# MCU_Control.net
KiCad netlist of a schematic drawn in Altium Designer
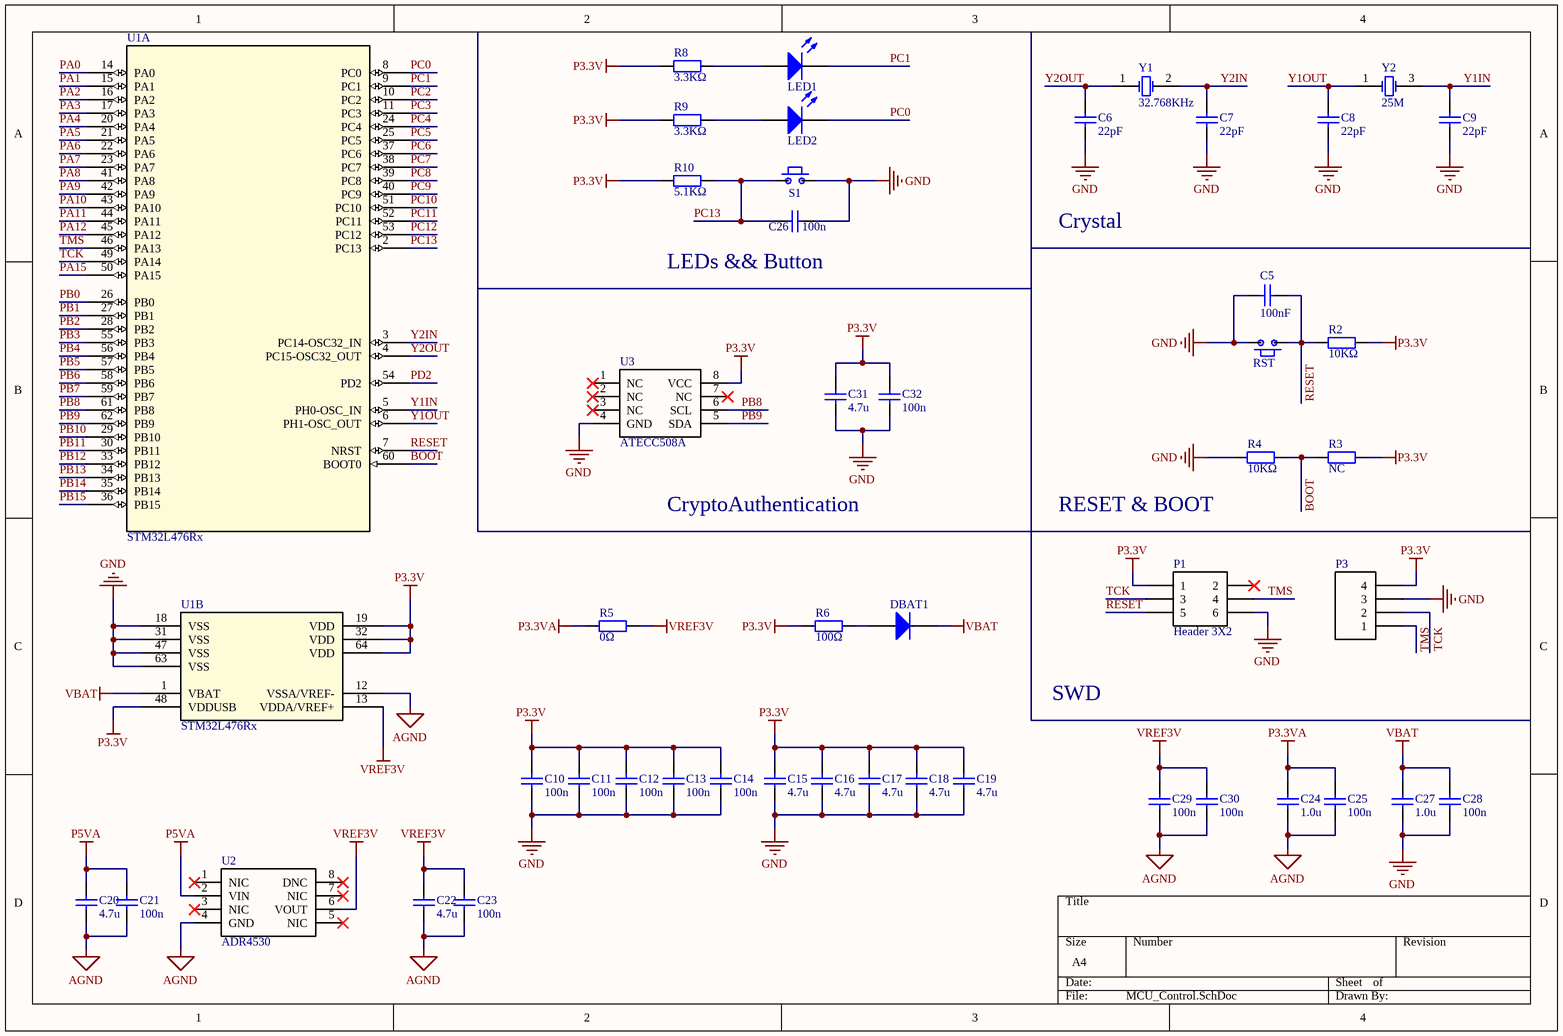
[diagram p0: MCU_Control.SchDoc]

(export (version "E")
  (design (tool "Eeschema 10.0.6"))
  (components
    (comp (ref "C5")
      (value "100nF")
      (footprint "0402_C")
      (description "贴片电容")
      (libsource (lib "Miscellaneous Devices LC") (part "0402 100nF (104) 10% 16V"))
    )
    (comp (ref "C6")
      (value "22pF")
      (footprint "0402_C")
      (description "贴片电容")
      (libsource (lib "Miscellaneous Devices LC") (part "0402 22pF (220) 5% 50V"))
    )
    (comp (ref "C7")
      (value "22pF")
      (footprint "0402_C")
      (description "贴片电容")
      (libsource (lib "Miscellaneous Devices LC") (part "0402 22pF (220) 5% 50V"))
    )
    (comp (ref "C8")
      (value "22pF")
      (footprint "0402_C")
      (description "贴片电容")
      (libsource (lib "Miscellaneous Devices LC") (part "0402 22pF (220) 5% 50V"))
    )
    (comp (ref "C9")
      (value "22pF")
      (footprint "0402_C")
      (description "贴片电容")
      (libsource (lib "Miscellaneous Devices LC") (part "0402 22pF (220) 5% 50V"))
    )
    (comp (ref "C10")
      (value "100n")
      (footprint "0402_C")
      (description "贴片电容")
      (libsource (lib "Miscellaneous Devices LC") (part "0402 100nF (104) 10% 16V"))
    )
    (comp (ref "C11")
      (value "100n")
      (footprint "0402_C")
      (description "贴片电容")
      (libsource (lib "Miscellaneous Devices LC") (part "0402 100nF (104) 10% 16V"))
    )
    (comp (ref "C12")
      (value "100n")
      (footprint "0402_C")
      (description "贴片电容")
      (libsource (lib "Miscellaneous Devices LC") (part "0402 100nF (104) 10% 16V"))
    )
    (comp (ref "C13")
      (value "100n")
      (footprint "0402_C")
      (description "贴片电容")
      (libsource (lib "Miscellaneous Devices LC") (part "0402 100nF (104) 10% 16V"))
    )
    (comp (ref "C14")
      (value "100n")
      (footprint "0402_C")
      (description "贴片电容")
      (libsource (lib "Miscellaneous Devices LC") (part "0402 100nF (104) 10% 16V"))
    )
    (comp (ref "C15")
      (value "4.7u")
      (footprint "0402_C")
      (description "贴片电容")
      (libsource (lib "Miscellaneous Devices LC") (part "0402 4.7uF (475) 20% 10V"))
    )
    (comp (ref "C16")
      (value "4.7u")
      (footprint "0402_C")
      (description "贴片电容")
      (libsource (lib "Miscellaneous Devices LC") (part "0402 4.7uF (475) 20% 10V"))
    )
    (comp (ref "C17")
      (value "4.7u")
      (footprint "0402_C")
      (description "贴片电容")
      (libsource (lib "Miscellaneous Devices LC") (part "0402 4.7uF (475) 20% 10V"))
    )
    (comp (ref "C18")
      (value "4.7u")
      (footprint "0402_C")
      (description "贴片电容")
      (libsource (lib "Miscellaneous Devices LC") (part "0402 4.7uF (475) 20% 10V"))
    )
    (comp (ref "C19")
      (value "4.7u")
      (footprint "0402_C")
      (description "贴片电容")
      (libsource (lib "Miscellaneous Devices LC") (part "0402 4.7uF (475) 20% 10V"))
    )
    (comp (ref "C20")
      (value "4.7u")
      (footprint "0402_C")
      (description "贴片电容")
      (libsource (lib "Miscellaneous Devices LC") (part "0402 4.7uF (475) 20% 10V"))
    )
    (comp (ref "C21")
      (value "100n")
      (footprint "0402_C")
      (description "贴片电容")
      (libsource (lib "Miscellaneous Devices LC") (part "0402 100nF (104) 10% 16V"))
    )
    (comp (ref "C22")
      (value "4.7u")
      (footprint "0402_C")
      (description "贴片电容")
      (libsource (lib "Miscellaneous Devices LC") (part "0402 4.7uF (475) 20% 10V"))
    )
    (comp (ref "C23")
      (value "100n")
      (footprint "0402_C")
      (description "贴片电容")
      (libsource (lib "Miscellaneous Devices LC") (part "0402 100nF (104) 10% 16V"))
    )
    (comp (ref "C24")
      (value "1.0u")
      (footprint "0402_C")
      (description "贴片电容")
      (libsource (lib "Miscellaneous Devices LC") (part "0402 1.0uF (105) 10% 25V"))
    )
    (comp (ref "C25")
      (value "100n")
      (footprint "0402_C")
      (description "贴片电容")
      (libsource (lib "Miscellaneous Devices LC") (part "0402 100nF (104) 10% 16V"))
    )
    (comp (ref "C26")
      (value "100n")
      (footprint "0402_C")
      (description "贴片电容")
      (libsource (lib "Miscellaneous Devices LC") (part "0402 100nF (104) 10% 16V"))
    )
    (comp (ref "C27")
      (value "1.0u")
      (footprint "0402_C")
      (description "贴片电容")
      (libsource (lib "Miscellaneous Devices LC") (part "0402 1.0uF (105) 10% 25V"))
    )
    (comp (ref "C28")
      (value "100n")
      (footprint "0402_C")
      (description "贴片电容")
      (libsource (lib "Miscellaneous Devices LC") (part "0402 100nF (104) 10% 16V"))
    )
    (comp (ref "C29")
      (value "100n")
      (footprint "0402_C")
      (description "贴片电容")
      (libsource (lib "Miscellaneous Devices LC") (part "0402 100nF (104) 10% 16V"))
    )
    (comp (ref "C30")
      (value "100n")
      (footprint "0402_C")
      (description "贴片电容")
      (libsource (lib "Miscellaneous Devices LC") (part "0402 100nF (104) 10% 16V"))
    )
    (comp (ref "C31")
      (value "4.7u")
      (footprint "0402_C")
      (description "贴片电容")
      (libsource (lib "Miscellaneous Devices LC") (part "0402 4.7uF (475) 20% 10V"))
    )
    (comp (ref "C32")
      (value "100n")
      (footprint "0402_C")
      (description "贴片电容")
      (libsource (lib "Miscellaneous Devices LC") (part "0402 100nF (104) 10% 16V"))
    )
    (comp (ref "DBAT1")
      (value "B5819W  SL")
      (footprint "SOD-123")
      (description "肖特基二极管")
      (libsource (lib "Miscellaneous Devices LC") (part "SOD-123 B5819W  SL"))
    )
    (comp (ref "LED1")
      (value "蓝灯 0603")
      (footprint "0603_LED_S1")
      (description "发光二极管")
      (libsource (lib "Miscellaneous Devices LC") (part "0603 蓝灯"))
    )
    (comp (ref "LED2")
      (value "蓝灯 0603")
      (footprint "0603_LED_S1")
      (description "发光二极管")
      (libsource (lib "Miscellaneous Devices LC") (part "0603 蓝灯"))
    )
    (comp (ref "P1")
      (value "Header 3X2")
      (footprint "DIP6-2.00-BH2")
      (description "Header, 3-Pin, Dual row")
      (libsource (lib "Connectors") (part "Header 3X2"))
    )
    (comp (ref "P3")
      (value "Header 4")
      (footprint "DIP4-2.00")
      (description "Header, 4-Pin")
      (fields (field (name "PUBLISHER") "Altium Limited"))
      (libsource (lib "Connectors") (part "Header 4"))
    )
    (comp (ref "R2")
      (value "10KΩ")
      (footprint "0402_R")
      (description "贴片电阻")
      (libsource (lib "Miscellaneous Devices LC") (part "0402 10KΩ (1002) 1%"))
    )
    (comp (ref "R3")
      (value "NC")
      (footprint "0402_R")
      (description "贴片电阻")
      (libsource (lib "Miscellaneous Devices LC") (part "0402 10KΩ (1002) 1%"))
    )
    (comp (ref "R4")
      (value "10KΩ")
      (footprint "0402_R")
      (description "贴片电阻")
      (libsource (lib "Miscellaneous Devices LC") (part "0402 10KΩ (1002) 1%"))
    )
    (comp (ref "R5")
      (value "0Ω")
      (footprint "0402_R")
      (description "贴片电阻")
      (libsource (lib "Miscellaneous Devices LC") (part "0402 0Ω (0R0) 1%"))
    )
    (comp (ref "R6")
      (value "100Ω")
      (footprint "0402_R")
      (description "贴片电阻")
      (libsource (lib "Miscellaneous Devices LC") (part "0402 100Ω (1000) 1%"))
    )
    (comp (ref "R8")
      (value "3.3KΩ")
      (footprint "0402_R")
      (description "贴片电阻")
      (libsource (lib "Miscellaneous Devices LC") (part "0402 3.3KΩ (3301) 1%"))
    )
    (comp (ref "R9")
      (value "3.3KΩ")
      (footprint "0402_R")
      (description "贴片电阻")
      (libsource (lib "Miscellaneous Devices LC") (part "0402 3.3KΩ (3301) 1%"))
    )
    (comp (ref "R10")
      (value "5.1KΩ")
      (footprint "0402_R")
      (description "贴片电阻")
      (libsource (lib "Miscellaneous Devices LC") (part "0402 5.1KΩ (5101) 1%"))
    )
    (comp (ref "RST")
      (value "Button")
      (footprint "SKRKAHE020")
      (libsource (lib "Connectors") (part "Button"))
    )
    (comp (ref "S1") (value "Button") (footprint "SKRKAHE020") (libsource (lib "Connectors") (part "Button")))
    (comp (ref "U1")
      (value "STM32L476Rx")
      (footprint "LQFP64-10x10mm")
      (fields
        (field (name "MANUFACTURER_PART_NUMBER") "stm32l486rx")
        (field (name "COPYRIGHT") "Copyright (C) 2016 Accelerated Designs. All rights reserved")
      )
      (libsource (lib "IC") (part "STM32L476Rx"))
    )
    (comp (ref "U2")
      (value "ADR4530")
      (footprint "SOIC-8-39mm")
      (description "Ultra-Low-Noise, High-Accuracy 3.0V Voltage Reference")
      (libsource (lib "IC") (part "ADR4530"))
    )
    (comp (ref "U3")
      (value "ATECC508A")
      (footprint "SOIC-8-39mm")
      (description "Security ICs / Authentication ICs")
      (libsource (lib "IC") (part "ATECC508A"))
    )
    (comp (ref "Y1")
      (value "32.768KHz")
      (footprint "SMD-3215_2P FC - 135")
      (description "贴片晶振")
      (libsource (lib "Miscellaneous Devices LC") (part "SMD-3215_2P 32.768KHz 20ppm 12.5pF"))
    )
    (comp (ref "Y2")
      (value "25M")
      (footprint "SMD-3225_4P")
      (description "贴片晶振")
      (libsource (lib "Miscellaneous Devices LC") (part "SMD-3225_4P  25MHZ 12PF 10PPM"))
    )
  )
  (nets
    (net (code "1") (name "/BOOT") (class "Default")
      (node (ref "R3") (pin "1") (pinfunction "1_1") (pintype "passive"))
      (node (ref "R4") (pin "2") (pinfunction "2_2") (pintype "passive"))
      (node (ref "U1") (pin "60") (pinfunction "BOOT0_60") (pintype "input"))
    )
    (net (code "2") (name "/PA0") (class "Default")
      (node (ref "U1") (pin "14") (pinfunction "PA0_14") (pintype "bidirectional"))
    )
    (net (code "3") (name "/PA1") (class "Default")
      (node (ref "U1") (pin "15") (pinfunction "PA1_15") (pintype "bidirectional"))
    )
    (net (code "4") (name "/PA2") (class "Default")
      (node (ref "U1") (pin "16") (pinfunction "PA2_16") (pintype "bidirectional"))
    )
    (net (code "5") (name "/PA3") (class "Default")
      (node (ref "U1") (pin "17") (pinfunction "PA3_17") (pintype "bidirectional"))
    )
    (net (code "6") (name "/PA4") (class "Default")
      (node (ref "U1") (pin "20") (pinfunction "PA4_20") (pintype "bidirectional"))
    )
    (net (code "7") (name "/PA5") (class "Default")
      (node (ref "U1") (pin "21") (pinfunction "PA5_21") (pintype "bidirectional"))
    )
    (net (code "8") (name "/PA6") (class "Default")
      (node (ref "U1") (pin "22") (pinfunction "PA6_22") (pintype "bidirectional"))
    )
    (net (code "9") (name "/PA7") (class "Default")
      (node (ref "U1") (pin "23") (pinfunction "PA7_23") (pintype "bidirectional"))
    )
    (net (code "10") (name "/PA8") (class "Default")
      (node (ref "U1") (pin "41") (pinfunction "PA8_41") (pintype "bidirectional"))
    )
    (net (code "11") (name "/PA9") (class "Default")
      (node (ref "U1") (pin "42") (pinfunction "PA9_42") (pintype "bidirectional"))
    )
    (net (code "12") (name "/PA10") (class "Default")
      (node (ref "U1") (pin "43") (pinfunction "PA10_43") (pintype "bidirectional"))
    )
    (net (code "13") (name "/PA11") (class "Default")
      (node (ref "U1") (pin "44") (pinfunction "PA11_44") (pintype "bidirectional"))
    )
    (net (code "14") (name "/PA12") (class "Default")
      (node (ref "U1") (pin "45") (pinfunction "PA12_45") (pintype "bidirectional"))
    )
    (net (code "15") (name "/PA15") (class "Default")
      (node (ref "U1") (pin "50") (pinfunction "PA15_50") (pintype "bidirectional"))
    )
    (net (code "16") (name "/PB0") (class "Default")
      (node (ref "U1") (pin "26") (pinfunction "PB0_26") (pintype "bidirectional"))
    )
    (net (code "17") (name "/PB1") (class "Default")
      (node (ref "U1") (pin "27") (pinfunction "PB1_27") (pintype "bidirectional"))
    )
    (net (code "18") (name "/PB2") (class "Default")
      (node (ref "U1") (pin "28") (pinfunction "PB2_28") (pintype "bidirectional"))
    )
    (net (code "19") (name "/PB3") (class "Default")
      (node (ref "U1") (pin "55") (pinfunction "PB3_55") (pintype "bidirectional"))
    )
    (net (code "20") (name "/PB4") (class "Default")
      (node (ref "U1") (pin "56") (pinfunction "PB4_56") (pintype "bidirectional"))
    )
    (net (code "21") (name "/PB5") (class "Default")
      (node (ref "U1") (pin "57") (pinfunction "PB5_57") (pintype "bidirectional"))
    )
    (net (code "22") (name "/PB6") (class "Default")
      (node (ref "U1") (pin "58") (pinfunction "PB6_58") (pintype "bidirectional"))
    )
    (net (code "23") (name "/PB7") (class "Default")
      (node (ref "U1") (pin "59") (pinfunction "PB7_59") (pintype "bidirectional"))
    )
    (net (code "24") (name "/PB8") (class "Default")
      (node (ref "U1") (pin "61") (pinfunction "PB8_61") (pintype "bidirectional"))
      (node (ref "U3") (pin "6") (pinfunction "SCL_6") (pintype "passive"))
    )
    (net (code "25") (name "/PB9") (class "Default")
      (node (ref "U1") (pin "62") (pinfunction "PB9_62") (pintype "bidirectional"))
      (node (ref "U3") (pin "5") (pinfunction "SDA_5") (pintype "passive"))
    )
    (net (code "26") (name "/PB10") (class "Default")
      (node (ref "U1") (pin "29") (pinfunction "PB10_29") (pintype "bidirectional"))
    )
    (net (code "27") (name "/PB11") (class "Default")
      (node (ref "U1") (pin "30") (pinfunction "PB11_30") (pintype "bidirectional"))
    )
    (net (code "28") (name "/PB12") (class "Default")
      (node (ref "U1") (pin "33") (pinfunction "PB12_33") (pintype "bidirectional"))
    )
    (net (code "29") (name "/PB13") (class "Default")
      (node (ref "U1") (pin "34") (pinfunction "PB13_34") (pintype "bidirectional"))
    )
    (net (code "30") (name "/PB14") (class "Default")
      (node (ref "U1") (pin "35") (pinfunction "PB14_35") (pintype "bidirectional"))
    )
    (net (code "31") (name "/PB15") (class "Default")
      (node (ref "U1") (pin "36") (pinfunction "PB15_36") (pintype "bidirectional"))
    )
    (net (code "32") (name "/PC0") (class "Default")
      (node (ref "LED2") (pin "K") (pinfunction "K_K") (pintype "passive"))
      (node (ref "U1") (pin "8") (pinfunction "PC0_8") (pintype "bidirectional"))
    )
    (net (code "33") (name "/PC1") (class "Default")
      (node (ref "LED1") (pin "K") (pinfunction "K_K") (pintype "passive"))
      (node (ref "U1") (pin "9") (pinfunction "PC1_9") (pintype "bidirectional"))
    )
    (net (code "34") (name "/PC2") (class "Default")
      (node (ref "U1") (pin "10") (pinfunction "PC2_10") (pintype "bidirectional"))
    )
    (net (code "35") (name "/PC3") (class "Default")
      (node (ref "U1") (pin "11") (pinfunction "PC3_11") (pintype "bidirectional"))
    )
    (net (code "36") (name "/PC4") (class "Default")
      (node (ref "U1") (pin "24") (pinfunction "PC4_24") (pintype "bidirectional"))
    )
    (net (code "37") (name "/PC5") (class "Default")
      (node (ref "U1") (pin "25") (pinfunction "PC5_25") (pintype "bidirectional"))
    )
    (net (code "38") (name "/PC6") (class "Default")
      (node (ref "U1") (pin "37") (pinfunction "PC6_37") (pintype "bidirectional"))
    )
    (net (code "39") (name "/PC7") (class "Default")
      (node (ref "U1") (pin "38") (pinfunction "PC7_38") (pintype "bidirectional"))
    )
    (net (code "40") (name "/PC8") (class "Default")
      (node (ref "U1") (pin "39") (pinfunction "PC8_39") (pintype "bidirectional"))
    )
    (net (code "41") (name "/PC9") (class "Default")
      (node (ref "U1") (pin "40") (pinfunction "PC9_40") (pintype "bidirectional"))
    )
    (net (code "42") (name "/PC10") (class "Default")
      (node (ref "U1") (pin "51") (pinfunction "PC10_51") (pintype "bidirectional"))
    )
    (net (code "43") (name "/PC11") (class "Default")
      (node (ref "U1") (pin "52") (pinfunction "PC11_52") (pintype "bidirectional"))
    )
    (net (code "44") (name "/PC12") (class "Default")
      (node (ref "U1") (pin "53") (pinfunction "PC12_53") (pintype "bidirectional"))
    )
    (net (code "45") (name "/PC13") (class "Default")
      (node (ref "C26") (pin "1") (pinfunction "1_1") (pintype "passive"))
      (node (ref "R10") (pin "2") (pinfunction "2_2") (pintype "passive"))
      (node (ref "S1") (pin "1") (pinfunction "1_1") (pintype "passive"))
      (node (ref "U1") (pin "2") (pinfunction "PC13_2") (pintype "bidirectional"))
    )
    (net (code "46") (name "/PD2") (class "Default")
      (node (ref "U1") (pin "54") (pinfunction "PD2_54") (pintype "bidirectional"))
    )
    (net (code "47") (name "/RESET") (class "Default")
      (node (ref "C5") (pin "2") (pinfunction "2_2") (pintype "passive"))
      (node (ref "P1") (pin "5") (pinfunction "5_5") (pintype "passive"))
      (node (ref "R2") (pin "1") (pinfunction "1_1") (pintype "passive"))
      (node (ref "RST") (pin "1") (pinfunction "1_1") (pintype "passive"))
      (node (ref "U1") (pin "7") (pinfunction "NRST_7") (pintype "bidirectional"))
    )
    (net (code "48") (name "/TCK") (class "Default")
      (node (ref "P1") (pin "3") (pinfunction "3_3") (pintype "passive"))
      (node (ref "P3") (pin "2") (pinfunction "2_2") (pintype "passive"))
      (node (ref "U1") (pin "49") (pinfunction "PA14_49") (pintype "bidirectional"))
    )
    (net (code "49") (name "/TMS") (class "Default")
      (node (ref "P1") (pin "4") (pinfunction "4_4") (pintype "passive"))
      (node (ref "P3") (pin "1") (pinfunction "1_1") (pintype "passive"))
      (node (ref "U1") (pin "46") (pinfunction "PA13_46") (pintype "bidirectional"))
    )
    (net (code "50") (name "/Y1IN") (class "Default")
      (node (ref "C9") (pin "2") (pinfunction "2_2") (pintype "passive"))
      (node (ref "U1") (pin "5") (pinfunction "PH0-OSC_IN_5") (pintype "bidirectional"))
      (node (ref "Y2") (pin "3") (pinfunction "OSC2_3") (pintype "passive"))
    )
    (net (code "51") (name "/Y1OUT") (class "Default")
      (node (ref "C8") (pin "2") (pinfunction "2_2") (pintype "passive"))
      (node (ref "U1") (pin "6") (pinfunction "PH1-OSC_OUT_6") (pintype "bidirectional"))
      (node (ref "Y2") (pin "1") (pinfunction "OSC1_1") (pintype "passive"))
    )
    (net (code "52") (name "/Y2IN") (class "Default")
      (node (ref "C7") (pin "2") (pinfunction "2_2") (pintype "passive"))
      (node (ref "U1") (pin "3") (pinfunction "PC14-OSC32_IN_3") (pintype "bidirectional"))
      (node (ref "Y1") (pin "2") (pinfunction "OSC2_2") (pintype "passive"))
    )
    (net (code "53") (name "/Y2OUT") (class "Default")
      (node (ref "C6") (pin "2") (pinfunction "2_2") (pintype "passive"))
      (node (ref "U1") (pin "4") (pinfunction "PC15-OSC32_OUT_4") (pintype "bidirectional"))
      (node (ref "Y1") (pin "1") (pinfunction "OSC1_1") (pintype "passive"))
    )
    (net (code "54") (name "AGND") (class "Default")
      (node (ref "C20") (pin "1") (pinfunction "1_1") (pintype "passive"))
      (node (ref "C21") (pin "1") (pinfunction "1_1") (pintype "passive"))
      (node (ref "C22") (pin "1") (pinfunction "1_1") (pintype "passive"))
      (node (ref "C23") (pin "1") (pinfunction "1_1") (pintype "passive"))
      (node (ref "C24") (pin "1") (pinfunction "1_1") (pintype "passive"))
      (node (ref "C25") (pin "1") (pinfunction "1_1") (pintype "passive"))
      (node (ref "C29") (pin "1") (pinfunction "1_1") (pintype "passive"))
      (node (ref "C30") (pin "1") (pinfunction "1_1") (pintype "passive"))
      (node (ref "U1") (pin "12") (pinfunction "VSSA/VREF-_12") (pintype "power_in"))
      (node (ref "U2") (pin "4") (pinfunction "GND_4") (pintype "passive"))
    )
    (net (code "55") (name "GND") (class "Default")
      (node (ref "C10") (pin "1") (pinfunction "1_1") (pintype "passive"))
      (node (ref "C11") (pin "1") (pinfunction "1_1") (pintype "passive"))
      (node (ref "C12") (pin "1") (pinfunction "1_1") (pintype "passive"))
      (node (ref "C13") (pin "1") (pinfunction "1_1") (pintype "passive"))
      (node (ref "C14") (pin "1") (pinfunction "1_1") (pintype "passive"))
      (node (ref "C15") (pin "1") (pinfunction "1_1") (pintype "passive"))
      (node (ref "C16") (pin "1") (pinfunction "1_1") (pintype "passive"))
      (node (ref "C17") (pin "1") (pinfunction "1_1") (pintype "passive"))
      (node (ref "C18") (pin "1") (pinfunction "1_1") (pintype "passive"))
      (node (ref "C19") (pin "1") (pinfunction "1_1") (pintype "passive"))
      (node (ref "C26") (pin "2") (pinfunction "2_2") (pintype "passive"))
      (node (ref "C27") (pin "1") (pinfunction "1_1") (pintype "passive"))
      (node (ref "C28") (pin "1") (pinfunction "1_1") (pintype "passive"))
      (node (ref "C31") (pin "1") (pinfunction "1_1") (pintype "passive"))
      (node (ref "C32") (pin "1") (pinfunction "1_1") (pintype "passive"))
      (node (ref "C5") (pin "1") (pinfunction "1_1") (pintype "passive"))
      (node (ref "C6") (pin "1") (pinfunction "1_1") (pintype "passive"))
      (node (ref "C7") (pin "1") (pinfunction "1_1") (pintype "passive"))
      (node (ref "C8") (pin "1") (pinfunction "1_1") (pintype "passive"))
      (node (ref "C9") (pin "1") (pinfunction "1_1") (pintype "passive"))
      (node (ref "P1") (pin "6") (pinfunction "6_6") (pintype "passive"))
      (node (ref "P3") (pin "3") (pinfunction "3_3") (pintype "passive"))
      (node (ref "R4") (pin "1") (pinfunction "1_1") (pintype "passive"))
      (node (ref "RST") (pin "2") (pinfunction "2_2") (pintype "passive"))
      (node (ref "S1") (pin "2") (pinfunction "2_2") (pintype "passive"))
      (node (ref "U1") (pin "18") (pinfunction "VSS_18") (pintype "power_in"))
      (node (ref "U1") (pin "31") (pinfunction "VSS_31") (pintype "power_in"))
      (node (ref "U1") (pin "47") (pinfunction "VSS_47") (pintype "power_in"))
      (node (ref "U1") (pin "63") (pinfunction "VSS_63") (pintype "power_in"))
      (node (ref "U3") (pin "4") (pinfunction "GND_4") (pintype "passive"))
    )
    (net (code "56") (name "Net-(DBAT1-A)") (class "Default")
      (node (ref "DBAT1") (pin "1") (pinfunction "A_1") (pintype "passive"))
      (node (ref "R6") (pin "2") (pinfunction "2_2") (pintype "passive"))
    )
    (net (code "57") (name "Net-(LED1-PadA)") (class "Default")
      (node (ref "LED1") (pin "A") (pinfunction "A_A") (pintype "passive"))
      (node (ref "R8") (pin "2") (pinfunction "2_2") (pintype "passive"))
    )
    (net (code "58") (name "Net-(LED2-PadA)") (class "Default")
      (node (ref "LED2") (pin "A") (pinfunction "A_A") (pintype "passive"))
      (node (ref "R9") (pin "2") (pinfunction "2_2") (pintype "passive"))
    )
    (net (code "59") (name "P3.3V") (class "Default")
      (node (ref "C10") (pin "2") (pinfunction "2_2") (pintype "passive"))
      (node (ref "C11") (pin "2") (pinfunction "2_2") (pintype "passive"))
      (node (ref "C12") (pin "2") (pinfunction "2_2") (pintype "passive"))
      (node (ref "C13") (pin "2") (pinfunction "2_2") (pintype "passive"))
      (node (ref "C14") (pin "2") (pinfunction "2_2") (pintype "passive"))
      (node (ref "C15") (pin "2") (pinfunction "2_2") (pintype "passive"))
      (node (ref "C16") (pin "2") (pinfunction "2_2") (pintype "passive"))
      (node (ref "C17") (pin "2") (pinfunction "2_2") (pintype "passive"))
      (node (ref "C18") (pin "2") (pinfunction "2_2") (pintype "passive"))
      (node (ref "C19") (pin "2") (pinfunction "2_2") (pintype "passive"))
      (node (ref "C31") (pin "2") (pinfunction "2_2") (pintype "passive"))
      (node (ref "C32") (pin "2") (pinfunction "2_2") (pintype "passive"))
      (node (ref "P1") (pin "1") (pinfunction "1_1") (pintype "passive"))
      (node (ref "P3") (pin "4") (pinfunction "4_4") (pintype "passive"))
      (node (ref "R10") (pin "1") (pinfunction "1_1") (pintype "passive"))
      (node (ref "R2") (pin "2") (pinfunction "2_2") (pintype "passive"))
      (node (ref "R3") (pin "2") (pinfunction "2_2") (pintype "passive"))
      (node (ref "R6") (pin "1") (pinfunction "1_1") (pintype "passive"))
      (node (ref "R8") (pin "1") (pinfunction "1_1") (pintype "passive"))
      (node (ref "R9") (pin "1") (pinfunction "1_1") (pintype "passive"))
      (node (ref "U1") (pin "19") (pinfunction "VDD_19") (pintype "power_in"))
      (node (ref "U1") (pin "32") (pinfunction "VDD_32") (pintype "power_in"))
      (node (ref "U1") (pin "48") (pinfunction "VDDUSB_48") (pintype "power_in"))
      (node (ref "U1") (pin "64") (pinfunction "VDD_64") (pintype "power_in"))
      (node (ref "U3") (pin "8") (pinfunction "VCC_8") (pintype "passive"))
    )
    (net (code "60") (name "P3.3VA") (class "Default")
      (node (ref "C24") (pin "2") (pinfunction "2_2") (pintype "passive"))
      (node (ref "C25") (pin "2") (pinfunction "2_2") (pintype "passive"))
      (node (ref "R5") (pin "1") (pinfunction "1_1") (pintype "passive"))
    )
    (net (code "61") (name "P5VA") (class "Default")
      (node (ref "C20") (pin "2") (pinfunction "2_2") (pintype "passive"))
      (node (ref "C21") (pin "2") (pinfunction "2_2") (pintype "passive"))
      (node (ref "U2") (pin "2") (pinfunction "VIN_2") (pintype "passive"))
    )
    (net (code "62") (name "VBAT") (class "Default")
      (node (ref "C27") (pin "2") (pinfunction "2_2") (pintype "passive"))
      (node (ref "C28") (pin "2") (pinfunction "2_2") (pintype "passive"))
      (node (ref "DBAT1") (pin "2") (pinfunction "K_2") (pintype "passive"))
      (node (ref "U1") (pin "1") (pinfunction "VBAT_1") (pintype "power_in"))
    )
    (net (code "63") (name "VREF3V") (class "Default")
      (node (ref "C22") (pin "2") (pinfunction "2_2") (pintype "passive"))
      (node (ref "C23") (pin "2") (pinfunction "2_2") (pintype "passive"))
      (node (ref "C29") (pin "2") (pinfunction "2_2") (pintype "passive"))
      (node (ref "C30") (pin "2") (pinfunction "2_2") (pintype "passive"))
      (node (ref "R5") (pin "2") (pinfunction "2_2") (pintype "passive"))
      (node (ref "U1") (pin "13") (pinfunction "VDDA/VREF+_13") (pintype "power_in"))
      (node (ref "U2") (pin "6") (pinfunction "VOUT_6") (pintype "passive"))
    )
    (net (code "64") (name "unconnected-(P1-Pad2)") (class "Default")
      (node (ref "P1") (pin "2") (pinfunction "2_2") (pintype "passive+no_connect"))
    )
    (net (code "65") (name "unconnected-(U2-DNC-Pad8)") (class "Default")
      (node (ref "U2") (pin "8") (pinfunction "DNC_8") (pintype "passive+no_connect"))
    )
    (net (code "66") (name "unconnected-(U2-NIC-Pad1)") (class "Default")
      (node (ref "U2") (pin "1") (pinfunction "NIC_1") (pintype "passive+no_connect"))
    )
    (net (code "67") (name "unconnected-(U2-NIC-Pad3)") (class "Default")
      (node (ref "U2") (pin "3") (pinfunction "NIC_3") (pintype "passive+no_connect"))
    )
    (net (code "68") (name "unconnected-(U2-NIC-Pad5)") (class "Default")
      (node (ref "U2") (pin "5") (pinfunction "NIC_5") (pintype "passive+no_connect"))
    )
    (net (code "69") (name "unconnected-(U2-NIC-Pad7)") (class "Default")
      (node (ref "U2") (pin "7") (pinfunction "NIC_7") (pintype "passive+no_connect"))
    )
    (net (code "70") (name "unconnected-(U3-NC-Pad1)") (class "Default")
      (node (ref "U3") (pin "1") (pinfunction "NC_1") (pintype "passive+no_connect"))
    )
    (net (code "71") (name "unconnected-(U3-NC-Pad2)") (class "Default")
      (node (ref "U3") (pin "2") (pinfunction "NC_2") (pintype "passive+no_connect"))
    )
    (net (code "72") (name "unconnected-(U3-NC-Pad3)") (class "Default")
      (node (ref "U3") (pin "3") (pinfunction "NC_3") (pintype "passive+no_connect"))
    )
    (net (code "73") (name "unconnected-(U3-NC-Pad7)") (class "Default")
      (node (ref "U3") (pin "7") (pinfunction "NC_7") (pintype "passive+no_connect"))
    )
  )
)
